# Circuit.net
KiCad netlist of a schematic drawn in Altium Designer
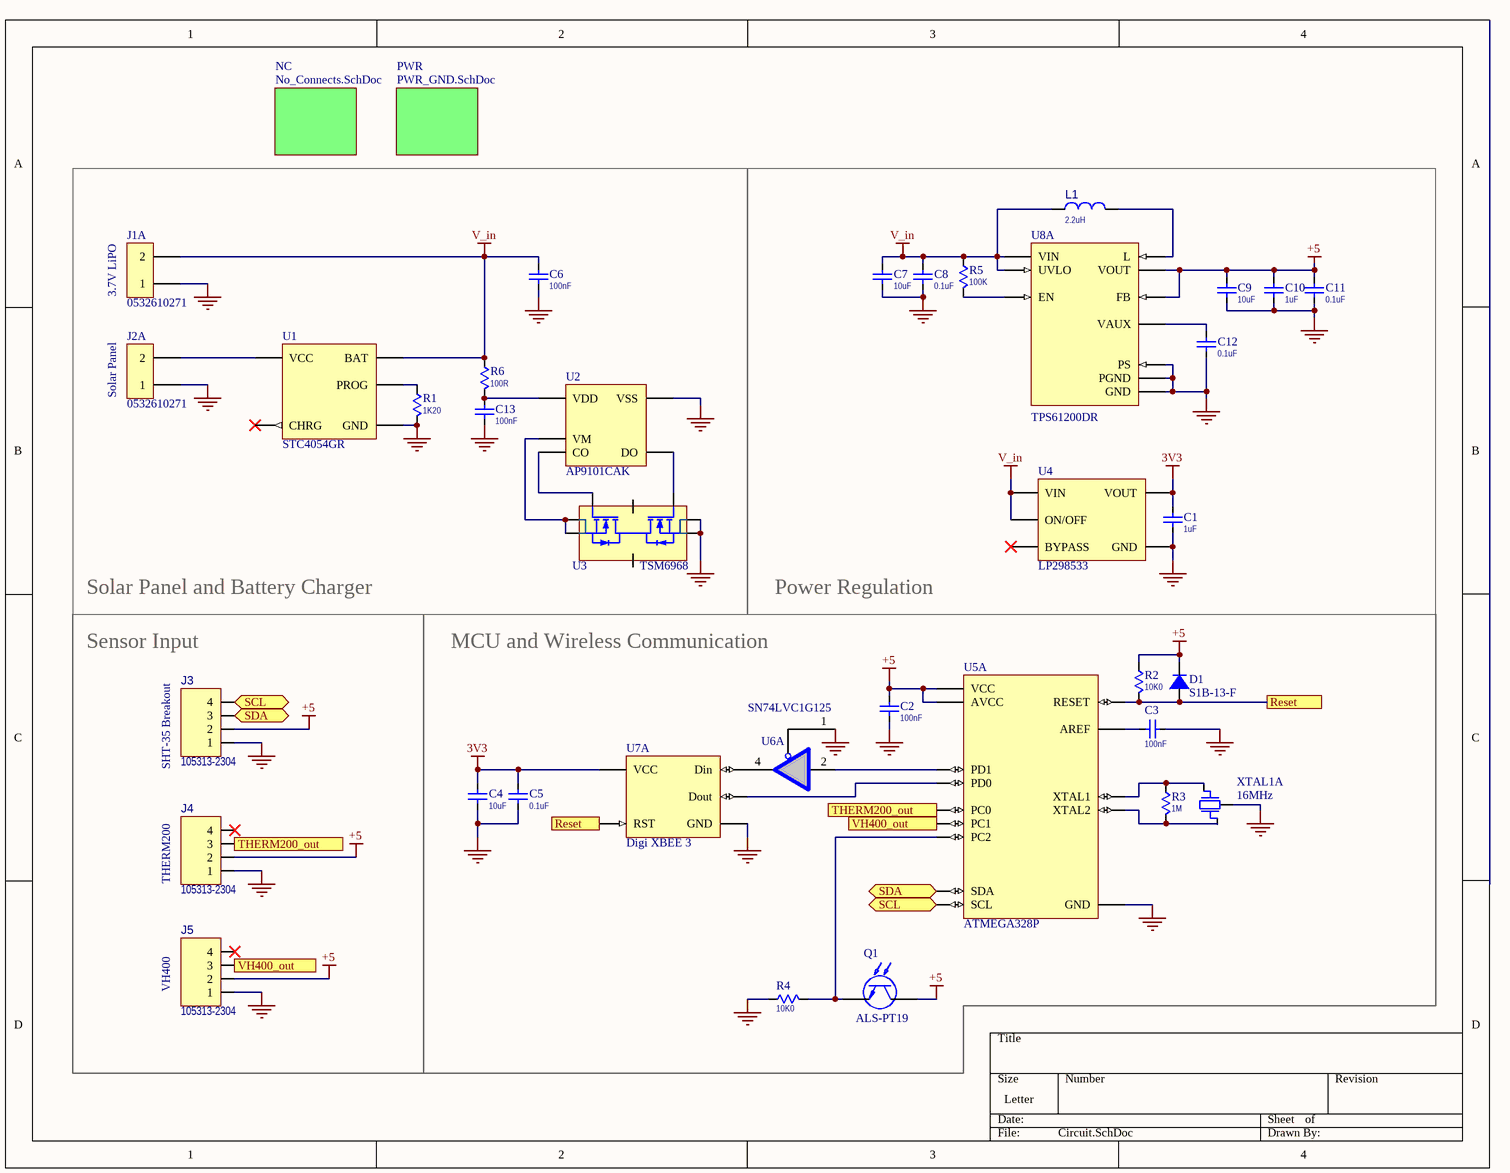
[diagram p0: Circuit.SchDoc]

(export (version "E")
  (design (tool "Eeschema 10.0.6"))
  (components
    (comp (ref "C1")
      (value "1uF")
      (footprint "CAP0603_HD")
      (description "CAP, 1.0uF, 50V, 10%, X7R, 0603(1608M)")
      (fields (field (name "MANF") "Taiyo Yuden") (field (name "TOLERANCE") "10%"))
      (libsource (lib "Passives") (part "CAP_1.0uF_50V_10%_X7R_0603(1608M)"))
    )
    (comp (ref "C2")
      (value "100nF")
      (footprint "CAP0603_HD")
      (description "CAP, 100nF, 100V, 10%, X7R, 0603(1608M)")
      (fields (field (name "MANF") "Murata") (field (name "TOLERANCE") "10%"))
      (libsource (lib "Passives") (part "CAP_100nF_100V_10%_X7R_0603(1608M)"))
    )
    (comp (ref "C3")
      (value "100nF")
      (footprint "CAP0603_HD")
      (description "CAP, 100nF, 100V, 10%, X7R, 0603(1608M)")
      (fields (field (name "MANF") "Murata") (field (name "TOLERANCE") "10%"))
      (libsource (lib "Passives") (part "CAP_100nF_100V_10%_X7R_0603(1608M)"))
    )
    (comp (ref "C4")
      (value "10uF")
      (footprint "CAP0603_HD")
      (description "CAP, 10uF, 10V, 15%, X5R, 0603(1608M)")
      (fields (field (name "MANF") "Murata") (field (name "TOLERANCE") "15%"))
      (libsource (lib "Passives") (part "CAP_10uF_10V_15%_X5R_0603(1608M)"))
    )
    (comp (ref "C5")
      (value "0.1uF")
      (footprint "CAP0402_HD")
      (description "CAP, 0.1uF, 25V, 10%, X7R, 0402(1005M)")
      (fields (field (name "MANF") "Samsung") (field (name "TOLERANCE") "10%"))
      (libsource (lib "Passives") (part "CAP_0.1uF_25V_10%_X7R_0402(1005M)"))
    )
    (comp (ref "C6")
      (value "100nF")
      (footprint "CAP0603_HD")
      (description "CAP, 100nF, 100V, 10%, X7R, 0603(1608M)")
      (fields (field (name "MANF") "Murata") (field (name "TOLERANCE") "10%"))
      (libsource (lib "Passives") (part "CAP_100nF_100V_10%_X7R_0603(1608M)"))
    )
    (comp (ref "C7")
      (value "10uF")
      (footprint "CAP0603_HD")
      (description "CAP, 10uF, 10V, 15%, X5R, 0603(1608M)")
      (fields (field (name "MANF") "Murata") (field (name "TOLERANCE") "15%"))
      (libsource (lib "Passives") (part "CAP_10uF_10V_15%_X5R_0603(1608M)"))
    )
    (comp (ref "C8")
      (value "0.1uF")
      (footprint "CAP0402_HD")
      (description "CAP, 0.1uF, 25V, 10%, X7R, 0402(1005M)")
      (fields (field (name "MANF") "Samsung") (field (name "TOLERANCE") "10%"))
      (libsource (lib "Passives") (part "CAP_0.1uF_25V_10%_X7R_0402(1005M)"))
    )
    (comp (ref "C9")
      (value "10uF")
      (footprint "CAP0603_HD")
      (description "CAP, 10uF, 10V, 15%, X5R, 0603(1608M)")
      (fields (field (name "MANF") "Murata") (field (name "TOLERANCE") "15%"))
      (libsource (lib "Passives") (part "CAP_10uF_10V_15%_X5R_0603(1608M)"))
    )
    (comp (ref "C10")
      (value "1uF")
      (footprint "CAP0603_HD")
      (description "CAP, 1.0uF, 50V, 10%, X7R, 0603(1608M)")
      (fields (field (name "MANF") "Taiyo Yuden") (field (name "TOLERANCE") "10%"))
      (libsource (lib "Passives") (part "CAP_1.0uF_50V_10%_X7R_0603(1608M)"))
    )
    (comp (ref "C11")
      (value "0.1uF")
      (footprint "CAP0402_HD")
      (description "CAP, 0.1uF, 25V, 10%, X7R, 0402(1005M)")
      (fields (field (name "MANF") "Samsung") (field (name "TOLERANCE") "10%"))
      (libsource (lib "Passives") (part "CAP_0.1uF_25V_10%_X7R_0402(1005M)"))
    )
    (comp (ref "C12")
      (value "0.1uF")
      (footprint "CAP0402_HD")
      (description "CAP, 0.1uF, 25V, 10%, X7R, 0402(1005M)")
      (fields (field (name "MANF") "Samsung") (field (name "TOLERANCE") "10%"))
      (libsource (lib "Passives") (part "CAP_0.1uF_25V_10%_X7R_0402(1005M)"))
    )
    (comp (ref "C13")
      (value "100nF")
      (footprint "CAP0603_HD")
      (description "CAP, 100nF, 100V, 10%, X7R, 0603(1608M)")
      (fields (field (name "MANF") "Murata") (field (name "TOLERANCE") "10%"))
      (libsource (lib "Passives") (part "CAP_100nF_100V_10%_X7R_0603(1608M)"))
    )
    (comp (ref "D1")
      (value "Diode_S1B-13-F")
      (footprint "SMA_DIODE")
      (fields (field (name "PART NUMBER") "S1B-13-F"))
      (libsource (lib "Actives") (part "Diode_S1B-13-F"))
    )
    (comp (ref "J1")
      (value "0532610271")
      (footprint "MOLEX_53261-0271")
      (description "2 Pos Molex Microblade")
      (fields (field (name "PART NUMBER") "0532610271"))
      (libsource (lib "Connectors") (part "0532610271"))
    )
    (comp (ref "J2")
      (value "0532610271")
      (footprint "MOLEX_53261-0271")
      (description "2 Pos Molex Microblade")
      (fields (field (name "PART NUMBER") "0532610271"))
      (libsource (lib "Connectors") (part "0532610271"))
    )
    (comp (ref "J3")
      (value "CON_105313-2304")
      (footprint "CON_105313-2304")
      (description "Connector, 2.5MM, 4 pos Singlel Row Header - Right Angle")
      (fields (field (name "MANF") "Molex") (field (name "MANF P/N") "105313-2304"))
      (libsource (lib "Connectors") (part "CON_105313-2304"))
    )
    (comp (ref "J4")
      (value "CON_105313-2304")
      (footprint "CON_105313-2304")
      (description "Connector, 2.5MM, 4 pos Singlel Row Header - Right Angle")
      (fields (field (name "MANF") "Molex") (field (name "MANF P/N") "105313-2304"))
      (libsource (lib "Connectors") (part "CON_105313-2304"))
    )
    (comp (ref "J5")
      (value "CON_105313-2304")
      (footprint "CON_105313-2304")
      (description "Connector, 2.5MM, 4 pos Singlel Row Header - Right Angle")
      (fields (field (name "MANF") "Molex") (field (name "MANF P/N") "105313-2304"))
      (libsource (lib "Connectors") (part "CON_105313-2304"))
    )
    (comp (ref "L1")
      (value "2.2uH")
      (footprint "IND_1616")
      (description "Inductor SMT, 27nH, Wire-wound Ceramic, 0402HP")
      (fields (field (name "MANF") "COILCRAFT") (field (name "Comment") "IND_2.2uH_WireWound"))
      (libsource (lib "Passives") (part "IND_2.2uH_WireWound"))
    )
    (comp (ref "Q1")
      (value "ALS-PT19 Phototransistor")
      (footprint "ALS-PT19 Phototransistor")
      (fields (field (name "PAT NUMBER") "ALS-PT19"))
      (libsource (lib "Actives") (part "ALS-PT19 Phototransistor"))
    )
    (comp (ref "R1")
      (value "1K20")
      (footprint "RES_0603_HD")
      (fields
        (field (name "TOLERANCE") "1%")
        (field (name "POWER") "0.05W")
        (field (name "MANF") "PANASONIC")
      )
      (libsource (lib "Passives") (part "RES_1.2K_0.1%_0.1W_0603"))
    )
    (comp (ref "R2")
      (value "10K0")
      (footprint "RES_0603_HD")
      (fields
        (field (name "TOLERANCE") "1%")
        (field (name "POWER") "0.33W")
        (field (name "MANF") "Vishay/Dale")
      )
      (libsource (lib "Passives") (part "RES_10.0K_1%_0.33W_0603"))
    )
    (comp (ref "R3")
      (value "1M")
      (footprint "RES_0603_HD")
      (fields
        (field (name "TOLERANCE") "1%")
        (field (name "POWER") "0.05W")
        (field (name "MANF") "PANASONIC")
      )
      (libsource (lib "Passives") (part "RES_1.00M_0.1%_0.1W_0603"))
    )
    (comp (ref "R4")
      (value "10K0")
      (footprint "RES_0603_HD")
      (fields
        (field (name "TOLERANCE") "1%")
        (field (name "POWER") "0.33W")
        (field (name "MANF") "Vishay/Dale")
      )
      (libsource (lib "Passives") (part "RES_10.0K_1%_0.33W_0603"))
    )
    (comp (ref "R5")
      (value "100K")
      (footprint "RES_0603_HD")
      (fields
        (field (name "TOLERANCE") "1%")
        (field (name "POWER") "0.05W")
        (field (name "MANF") "PANASONIC")
      )
      (libsource (lib "Passives") (part "RES_100K_0.1%_0.1W_0603"))
    )
    (comp (ref "R6")
      (value "100R")
      (footprint "RES_0603_HD")
      (fields (field (name "TOLERANCE") "1%") (field (name "MANF") "Vishay") (field (name "POWER") "0.05W"))
      (libsource (lib "Passives") (part "RES_100_0.5%_1/16W_0603"))
    )
    (comp (ref "U1")
      (value "STC4054GR")
      (footprint "TSOT-23-5")
      (description "800mA Standalone linear Li-ion charger with thermal regulation")
      (fields (field (name "PART NUMBER") "STC4054GR"))
      (libsource (lib "ICs") (part "STC4054GR"))
    )
    (comp (ref "U2")
      (value "AP9101CAK-ABTRG1")
      (footprint "SOT-25")
      (description "Battery Protection IC for LiPo")
      (fields (field (name "PART NUMBER") "AP9101CAK"))
      (libsource (lib "ICs") (part "AP9101CAK-ABTRG1"))
    )
    (comp (ref "U3")
      (value "TSM6968DCA")
      (footprint "8-TSSOP")
      (fields (field (name "PARAMETER 1") "TSM6968"))
      (libsource (lib "Actives") (part "TSM6968DCA"))
    )
    (comp (ref "U4")
      (value "LP298533DBVR Voltage Regulator")
      (footprint "SOT23-5")
      (description "Arduino 3.3v regulator")
      (fields (field (name "PART NUMBER") "LP298533"))
      (libsource (lib "ICs") (part "LP298533DBVR Voltage Regulator"))
    )
    (comp (ref "U5")
      (value "ATMEGA328P_SMD")
      (footprint "32A_ATM")
      (description "Arduino ATMEGA328 Chip")
      (fields (field (name "PART NUMBER") "ATMEGA328P"))
      (libsource (lib "ICs") (part "ATMEGA328P_SMD"))
    )
    (comp (ref "U6")
      (value "SN74LVC1G125DCKR")
      (footprint "SOT-SC70-5")
      (description "Single Bus 3-State Buffer")
      (fields (field (name "PART NUMBER") "SN74LVC1G125"))
      (libsource (lib "Actives") (part "SN74LVC1G125DCKR"))
    )
    (comp (ref "U7")
      (value "XBEE 3 SMD")
      (footprint "XBee_1W_Base")
      (fields (field (name "PART NUMBER") "Digi XBEE 3"))
      (libsource (lib "ICs") (part "XBEE 3 SMD"))
    )
    (comp (ref "U8")
      (value "TPS61200DR Voltage Boost Regulator")
      (footprint "10-VFDFN Exposed Pad")
      (description "Used on Pololu step up regulator board")
      (fields (field (name "PART NUMBER") "TPS61200DR"))
      (libsource (lib "ICs") (part "TPS61200DR Voltage Boost Regulator"))
    )
    (comp (ref "XTAL1")
      (value "16MHz")
      (footprint "OSC SMD-4")
      (description "16MHz Oscillator")
      (fields (field (name "Comment") "CX3225SB16000D0GZJC1"))
      (libsource (lib "Actives") (part "CX3225SB16000D0GZJC1"))
    )
  )
  (nets
    (net (code "1") (name "+5") (class "Default")
      (node (ref "C10") (pin "1") (pintype "passive"))
      (node (ref "C11") (pin "1") (pintype "passive"))
      (node (ref "C2") (pin "1") (pintype "passive"))
      (node (ref "C9") (pin "1") (pintype "passive"))
      (node (ref "D1") (pin "1") (pinfunction "1_1") (pintype "passive"))
      (node (ref "J3") (pin "2") (pinfunction "2_2") (pintype "passive"))
      (node (ref "J4") (pin "2") (pinfunction "2_2") (pintype "passive"))
      (node (ref "J5") (pin "2") (pinfunction "2_2") (pintype "passive"))
      (node (ref "Q1") (pin "2") (pinfunction "2_2") (pintype "passive"))
      (node (ref "R2") (pin "1") (pintype "passive"))
      (node (ref "U5") (pin "18") (pinfunction "AVCC_18") (pintype "power_in"))
      (node (ref "U5") (pin "4") (pinfunction "VCC_4") (pintype "power_in"))
      (node (ref "U8") (pin "10") (pinfunction "FB_10") (pintype "input"))
      (node (ref "U8") (pin "2") (pinfunction "VOUT_2") (pintype "power_in"))
    )
    (net (code "2") (name "/Reset") (class "Default")
      (node (ref "D1") (pin "2") (pinfunction "2_2") (pintype "passive"))
      (node (ref "R2") (pin "2") (pintype "passive"))
      (node (ref "U5") (pin "29") (pinfunction "RESET_29") (pintype "bidirectional"))
      (node (ref "U7") (pin "6") (pinfunction "RST_6") (pintype "input"))
    )
    (net (code "3") (name "/SCL") (class "Default")
      (node (ref "J3") (pin "4") (pinfunction "4_4") (pintype "passive"))
      (node (ref "U5") (pin "28") (pinfunction "SCL_28") (pintype "bidirectional"))
    )
    (net (code "4") (name "/SDA") (class "Default")
      (node (ref "J3") (pin "3") (pinfunction "3_3") (pintype "passive"))
      (node (ref "U5") (pin "27") (pinfunction "SDA_27") (pintype "bidirectional"))
    )
    (net (code "5") (name "/THERM200_out") (class "Default")
      (node (ref "J4") (pin "3") (pinfunction "3_3") (pintype "passive"))
      (node (ref "U5") (pin "23") (pinfunction "PC0_23") (pintype "bidirectional"))
    )
    (net (code "6") (name "/VH400_out") (class "Default")
      (node (ref "J5") (pin "3") (pinfunction "3_3") (pintype "passive"))
      (node (ref "U5") (pin "24") (pinfunction "PC1_24") (pintype "bidirectional"))
    )
    (net (code "7") (name "3V3") (class "Default")
      (node (ref "C1") (pin "1") (pintype "passive"))
      (node (ref "C4") (pin "1") (pintype "passive"))
      (node (ref "C5") (pin "1") (pintype "passive"))
      (node (ref "U4") (pin "5") (pinfunction "VOUT_5") (pintype "passive"))
      (node (ref "U7") (pin "2") (pinfunction "VCC_2") (pintype "power_in"))
    )
    (net (code "8") (name "GND") (class "Default")
      (node (ref "C1") (pin "2") (pintype "passive"))
      (node (ref "C10") (pin "2") (pintype "passive"))
      (node (ref "C11") (pin "2") (pintype "passive"))
      (node (ref "C12") (pin "2") (pintype "passive"))
      (node (ref "C13") (pin "2") (pintype "passive"))
      (node (ref "C2") (pin "2") (pintype "passive"))
      (node (ref "C3") (pin "2") (pintype "passive"))
      (node (ref "C4") (pin "2") (pintype "passive"))
      (node (ref "C5") (pin "2") (pintype "passive"))
      (node (ref "C6") (pin "2") (pintype "passive"))
      (node (ref "C7") (pin "2") (pintype "passive"))
      (node (ref "C8") (pin "2") (pintype "passive"))
      (node (ref "C9") (pin "2") (pintype "passive"))
      (node (ref "J1") (pin "1") (pinfunction "1_1") (pintype "passive"))
      (node (ref "J2") (pin "1") (pinfunction "1_1") (pintype "passive"))
      (node (ref "J3") (pin "1") (pinfunction "1_1") (pintype "passive"))
      (node (ref "J4") (pin "1") (pinfunction "1_1") (pintype "passive"))
      (node (ref "J5") (pin "1") (pinfunction "1_1") (pintype "passive"))
      (node (ref "R1") (pin "2") (pintype "passive"))
      (node (ref "R4") (pin "1") (pintype "passive"))
      (node (ref "U1") (pin "2") (pinfunction "GND_2") (pintype "passive"))
      (node (ref "U2") (pin "3") (pinfunction "VSS_3") (pintype "passive"))
      (node (ref "U3") (pin "6") (pinfunction "S2_6") (pintype "passive"))
      (node (ref "U3") (pin "7") (pinfunction "S2_7") (pintype "passive"))
      (node (ref "U4") (pin "2") (pinfunction "GND_2") (pintype "passive"))
      (node (ref "U5") (pin "5") (pinfunction "GND_5") (pintype "power_in"))
      (node (ref "U6") (pin "1") (pinfunction "OE_1") (pintype "passive"))
      (node (ref "U7") (pin "13") (pinfunction "GND_13") (pintype "power_in"))
      (node (ref "U8") (pin "11") (pinfunction "GND_11") (pintype "passive"))
      (node (ref "U8") (pin "4") (pinfunction "PGND_4") (pintype "power_in"))
      (node (ref "U8") (pin "8") (pinfunction "PS_8") (pintype "input"))
      (node (ref "XTAL1") (pin "2") (pinfunction "GND_2") (pintype "passive"))
    )
    (net (code "9") (name "Net-(U1-PROG)") (class "Default")
      (node (ref "R1") (pin "1") (pintype "passive"))
      (node (ref "U1") (pin "5") (pinfunction "PROG_5") (pintype "passive"))
    )
    (net (code "10") (name "Net-(U1-VCC)") (class "Default")
      (node (ref "J2") (pin "2") (pinfunction "2_2") (pintype "passive"))
      (node (ref "U1") (pin "4") (pinfunction "VCC_4") (pintype "passive"))
    )
    (net (code "11") (name "Net-(U2-CO)") (class "Default")
      (node (ref "U2") (pin "5") (pinfunction "CO_5") (pintype "passive"))
      (node (ref "U3") (pin "4") (pinfunction "G1_4") (pintype "passive"))
    )
    (net (code "12") (name "Net-(U2-DO)") (class "Default")
      (node (ref "U2") (pin "4") (pinfunction "DO_4") (pintype "passive"))
      (node (ref "U3") (pin "5") (pinfunction "G2_5") (pintype "passive"))
    )
    (net (code "13") (name "Net-(U2-VDD)") (class "Default")
      (node (ref "C13") (pin "1") (pintype "passive"))
      (node (ref "R6") (pin "2") (pintype "passive"))
      (node (ref "U2") (pin "2") (pinfunction "VDD_2") (pintype "passive"))
    )
    (net (code "14") (name "Net-(U2-VM)") (class "Default")
      (node (ref "U2") (pin "1") (pinfunction "VM_1") (pintype "passive"))
      (node (ref "U3") (pin "2") (pinfunction "S1_2") (pintype "passive"))
      (node (ref "U3") (pin "3") (pinfunction "S1_3") (pintype "passive"))
    )
    (net (code "15") (name "Net-(U5A-AREF)") (class "Default")
      (node (ref "C3") (pin "1") (pintype "passive"))
      (node (ref "U5") (pin "20") (pinfunction "AREF_20") (pintype "passive"))
    )
    (net (code "16") (name "Net-(U5A-PC2)") (class "Default")
      (node (ref "Q1") (pin "1") (pinfunction "1_1") (pintype "passive"))
      (node (ref "R4") (pin "2") (pintype "passive"))
      (node (ref "U5") (pin "25") (pinfunction "PC2_25") (pintype "bidirectional"))
    )
    (net (code "17") (name "Net-(U5A-PD0)") (class "Default")
      (node (ref "U5") (pin "30") (pinfunction "PD0_30") (pintype "bidirectional"))
      (node (ref "U7") (pin "3") (pinfunction "Dout_3") (pintype "bidirectional"))
    )
    (net (code "18") (name "Net-(U5A-PD1)") (class "Default")
      (node (ref "U5") (pin "31") (pinfunction "PD1_31") (pintype "bidirectional"))
      (node (ref "U6") (pin "2") (pinfunction "A_2") (pintype "passive"))
    )
    (net (code "19") (name "Net-(U5A-XTAL1)") (class "Default")
      (node (ref "R3") (pin "1") (pintype "passive"))
      (node (ref "U5") (pin "8") (pinfunction "XTAL1_8") (pintype "bidirectional"))
      (node (ref "XTAL1") (pin "1") (pinfunction "HOT_1") (pintype "passive"))
    )
    (net (code "20") (name "Net-(U5A-XTAL2)") (class "Default")
      (node (ref "R3") (pin "2") (pintype "passive"))
      (node (ref "U5") (pin "7") (pinfunction "XTAL2_7") (pintype "bidirectional"))
      (node (ref "XTAL1") (pin "3") (pinfunction "HOT_3") (pintype "passive"))
    )
    (net (code "21") (name "Net-(U6A-Y)") (class "Default")
      (node (ref "U6") (pin "4") (pinfunction "Y_4") (pintype "passive"))
      (node (ref "U7") (pin "4") (pinfunction "Din_4") (pintype "bidirectional"))
    )
    (net (code "22") (name "Net-(U8A-EN)") (class "Default")
      (node (ref "R5") (pin "2") (pintype "passive"))
      (node (ref "U8") (pin "6") (pinfunction "EN_6") (pintype "input"))
    )
    (net (code "23") (name "Net-(U8A-L)") (class "Default")
      (node (ref "L1") (pin "2") (pinfunction "2_2") (pintype "passive"))
      (node (ref "U8") (pin "3") (pinfunction "L_3") (pintype "input"))
    )
    (net (code "24") (name "Net-(U8A-VAUX)") (class "Default")
      (node (ref "C12") (pin "1") (pintype "passive"))
      (node (ref "U8") (pin "1") (pinfunction "VAUX_1") (pintype "power_in"))
    )
    (net (code "25") (name "V_in") (class "Default")
      (node (ref "C6") (pin "1") (pintype "passive"))
      (node (ref "C7") (pin "1") (pintype "passive"))
      (node (ref "C8") (pin "1") (pintype "passive"))
      (node (ref "J1") (pin "2") (pinfunction "2_2") (pintype "passive"))
      (node (ref "L1") (pin "1") (pinfunction "1_1") (pintype "passive"))
      (node (ref "R5") (pin "1") (pintype "passive"))
      (node (ref "R6") (pin "1") (pintype "passive"))
      (node (ref "U1") (pin "3") (pinfunction "BAT_3") (pintype "passive"))
      (node (ref "U4") (pin "1") (pinfunction "VIN_1") (pintype "passive"))
      (node (ref "U4") (pin "3") (pinfunction "ON/OFF_3") (pintype "passive"))
      (node (ref "U8") (pin "5") (pinfunction "VIN_5") (pintype "power_in"))
      (node (ref "U8") (pin "7") (pinfunction "UVLO_7") (pintype "input"))
    )
    (net (code "26") (name "unconnected-(J4-Pad4)") (class "Default")
      (node (ref "J4") (pin "4") (pinfunction "4_4") (pintype "passive+no_connect"))
    )
    (net (code "27") (name "unconnected-(J5-Pad4)") (class "Default")
      (node (ref "J5") (pin "4") (pinfunction "4_4") (pintype "passive+no_connect"))
    )
    (net (code "28") (name "unconnected-(U1-CHRG-Pad1)") (class "Default")
      (node (ref "U1") (pin "1") (pinfunction "CHRG_1") (pintype "output+no_connect"))
    )
    (net (code "29") (name "unconnected-(U3-D1-Pad8)") (class "Default")
      (node (ref "U3") (pin "8") (pinfunction "D1_8") (pintype "passive"))
    )
    (net (code "30") (name "unconnected-(U3-D2-Pad1)") (class "Default")
      (node (ref "U3") (pin "1") (pinfunction "D2_1") (pintype "passive"))
    )
    (net (code "31") (name "unconnected-(U4-BYPASS-Pad4)") (class "Default")
      (node (ref "U4") (pin "4") (pinfunction "BYPASS_4") (pintype "passive+no_connect"))
    )
  )
)
